# TestPoints.net
KiCad netlist of a schematic drawn in Altium Designer
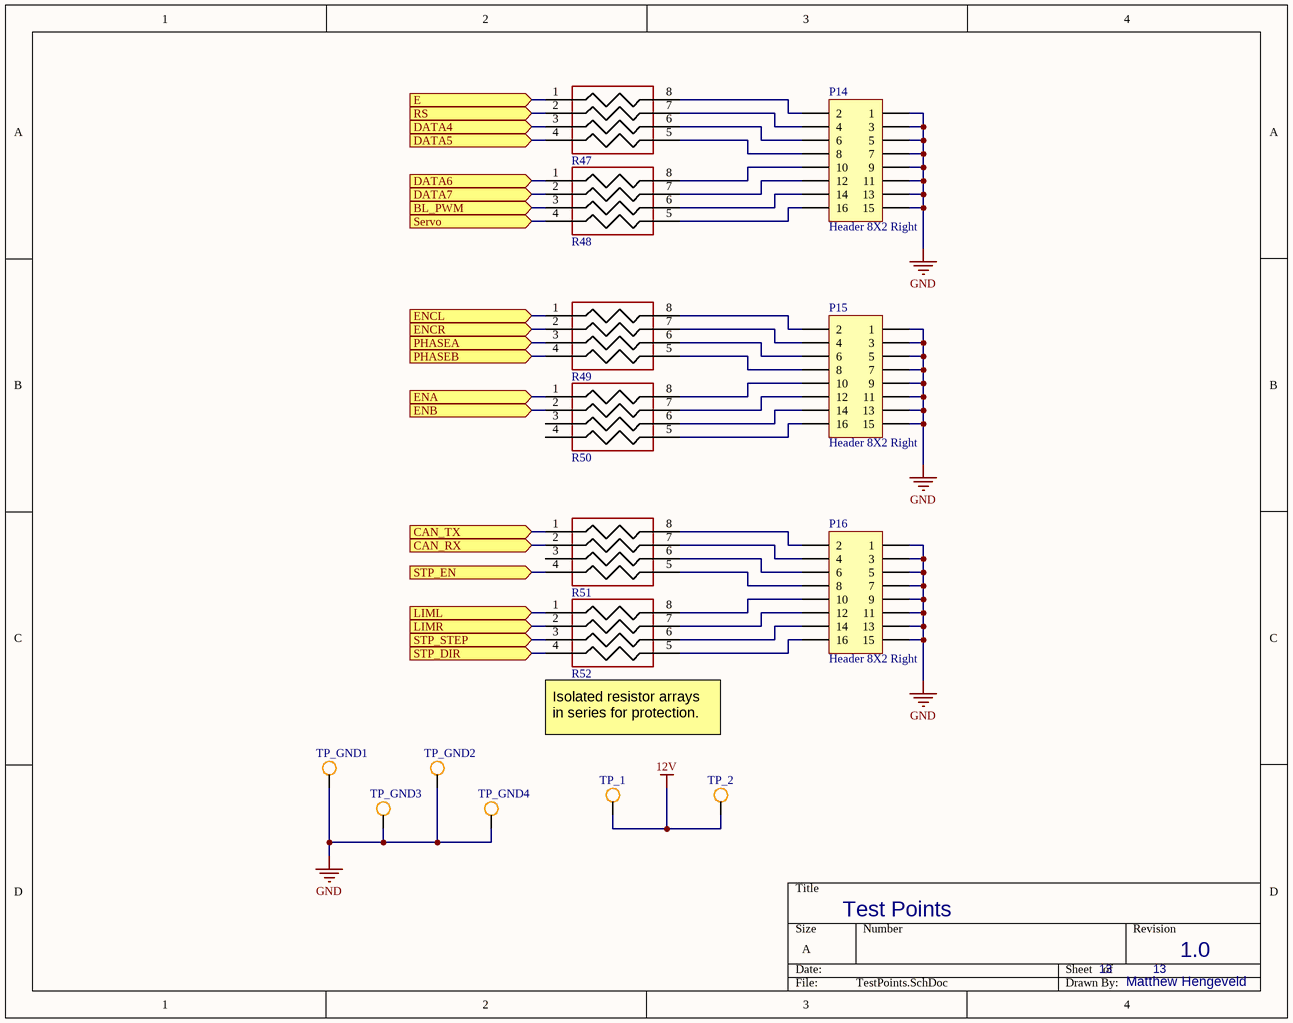
[diagram p0: TestPoints.SchDoc]

(export (version "E")
  (design (tool "Eeschema 10.0.6"))
  (components
    (comp (ref "P14")
      (value "Header 8X2 Right")
      (footprint "HDR2X8 RIGHT")
      (description "Header, 8-Pin, Dual row, Right Angle")
      (fields (field (name "PUBLISHER") "Altium Limited"))
      (libsource (lib "Hengeveld") (part "Header 8X2 Right"))
    )
    (comp (ref "P15")
      (value "Header 8X2 Right")
      (footprint "HDR2X8 RIGHT")
      (description "Header, 8-Pin, Dual row, Right Angle")
      (fields (field (name "PUBLISHER") "Altium Limited"))
      (libsource (lib "Hengeveld") (part "Header 8X2 Right"))
    )
    (comp (ref "P16")
      (value "Header 8X2 Right")
      (footprint "HDR2X8 RIGHT")
      (description "Header, 8-Pin, Dual row, Right Angle")
      (fields (field (name "PUBLISHER") "Altium Limited"))
      (libsource (lib "Hengeveld") (part "Header 8X2 Right"))
    )
    (comp (ref "R47")
      (value "8RES_ISO_ARRAY")
      (footprint "4RES_ARRAY_1206")
      (description "4 Resistor Array")
      (libsource (lib "Hengeveld") (part "8RES_ISO_ARRAY"))
    )
    (comp (ref "R48")
      (value "8RES_ISO_ARRAY")
      (footprint "4RES_ARRAY_1206")
      (description "4 Resistor Array")
      (libsource (lib "Hengeveld") (part "8RES_ISO_ARRAY"))
    )
    (comp (ref "R49")
      (value "8RES_ISO_ARRAY")
      (footprint "4RES_ARRAY_1206")
      (description "4 Resistor Array")
      (libsource (lib "Hengeveld") (part "8RES_ISO_ARRAY"))
    )
    (comp (ref "R50")
      (value "8RES_ISO_ARRAY")
      (footprint "4RES_ARRAY_1206")
      (description "4 Resistor Array")
      (libsource (lib "Hengeveld") (part "8RES_ISO_ARRAY"))
    )
    (comp (ref "R51")
      (value "8RES_ISO_ARRAY")
      (footprint "4RES_ARRAY_1206")
      (description "4 Resistor Array")
      (libsource (lib "Hengeveld") (part "8RES_ISO_ARRAY"))
    )
    (comp (ref "R52")
      (value "8RES_ISO_ARRAY")
      (footprint "4RES_ARRAY_1206")
      (description "4 Resistor Array")
      (libsource (lib "Hengeveld") (part "8RES_ISO_ARRAY"))
    )
    (comp (ref "TP_1")
      (value "Test point")
      (footprint "SMD Test Hook")
      (libsource (lib "Hengeveld") (part "Test Point"))
    )
    (comp (ref "TP_2")
      (value "Test point")
      (footprint "SMD Test Hook")
      (libsource (lib "Hengeveld") (part "Test Point"))
    )
    (comp (ref "TP_GND1")
      (value "Test point")
      (footprint "SMD Test Hook")
      (libsource (lib "Hengeveld") (part "Test Point"))
    )
    (comp (ref "TP_GND2")
      (value "Test point")
      (footprint "SMD Test Hook")
      (libsource (lib "Hengeveld") (part "Test Point"))
    )
    (comp (ref "TP_GND3")
      (value "Test point")
      (footprint "SMD Test Hook")
      (libsource (lib "Hengeveld") (part "Test Point"))
    )
    (comp (ref "TP_GND4")
      (value "Test point")
      (footprint "SMD Test Hook")
      (libsource (lib "Hengeveld") (part "Test Point"))
    )
  )
  (nets
    (net (code "1") (name "/BL_PWM") (class "Default")
      (node (ref "R48") (pin "3") (pinfunction "14_3") (pintype "passive"))
    )
    (net (code "2") (name "/CAN_RX") (class "Default")
      (node (ref "R51") (pin "2") (pinfunction "14_2") (pintype "passive"))
    )
    (net (code "3") (name "/CAN_TX") (class "Default")
      (node (ref "R51") (pin "1") (pinfunction "14_1") (pintype "passive"))
    )
    (net (code "4") (name "/DATA4") (class "Default")
      (node (ref "R47") (pin "3") (pinfunction "14_3") (pintype "passive"))
    )
    (net (code "5") (name "/DATA5") (class "Default")
      (node (ref "R47") (pin "4") (pinfunction "14_4") (pintype "passive"))
    )
    (net (code "6") (name "/DATA6") (class "Default")
      (node (ref "R48") (pin "1") (pinfunction "14_1") (pintype "passive"))
    )
    (net (code "7") (name "/DATA7") (class "Default")
      (node (ref "R48") (pin "2") (pinfunction "14_2") (pintype "passive"))
    )
    (net (code "8") (name "/E") (class "Default")
      (node (ref "R47") (pin "1") (pinfunction "14_1") (pintype "passive"))
    )
    (net (code "9") (name "/ENA") (class "Default")
      (node (ref "R50") (pin "1") (pinfunction "14_1") (pintype "passive"))
    )
    (net (code "10") (name "/ENB") (class "Default")
      (node (ref "R50") (pin "2") (pinfunction "14_2") (pintype "passive"))
    )
    (net (code "11") (name "/ENCL") (class "Default")
      (node (ref "R49") (pin "1") (pinfunction "14_1") (pintype "passive"))
    )
    (net (code "12") (name "/ENCR") (class "Default")
      (node (ref "R49") (pin "2") (pinfunction "14_2") (pintype "passive"))
    )
    (net (code "13") (name "/LIML") (class "Default")
      (node (ref "R52") (pin "1") (pinfunction "14_1") (pintype "passive"))
    )
    (net (code "14") (name "/LIMR") (class "Default")
      (node (ref "R52") (pin "2") (pinfunction "14_2") (pintype "passive"))
    )
    (net (code "15") (name "/PHASEA") (class "Default")
      (node (ref "R49") (pin "3") (pinfunction "14_3") (pintype "passive"))
    )
    (net (code "16") (name "/PHASEB") (class "Default")
      (node (ref "R49") (pin "4") (pinfunction "14_4") (pintype "passive"))
    )
    (net (code "17") (name "/RS") (class "Default")
      (node (ref "R47") (pin "2") (pinfunction "14_2") (pintype "passive"))
    )
    (net (code "18") (name "/STP_DIR") (class "Default")
      (node (ref "R52") (pin "4") (pinfunction "14_4") (pintype "passive"))
    )
    (net (code "19") (name "/STP_EN") (class "Default")
      (node (ref "R51") (pin "4") (pinfunction "14_4") (pintype "passive"))
    )
    (net (code "20") (name "/STP_STEP") (class "Default")
      (node (ref "R52") (pin "3") (pinfunction "14_3") (pintype "passive"))
    )
    (net (code "21") (name "/Servo") (class "Default")
      (node (ref "R48") (pin "4") (pinfunction "14_4") (pintype "passive"))
    )
    (net (code "22") (name "12V") (class "Default")
      (node (ref "TP_1") (pin "1") (pinfunction "point_1") (pintype "passive"))
      (node (ref "TP_2") (pin "1") (pinfunction "point_1") (pintype "passive"))
    )
    (net (code "23") (name "GND") (class "Default")
      (node (ref "P14") (pin "1") (pinfunction "1_1") (pintype "passive"))
      (node (ref "P14") (pin "11") (pinfunction "11_11") (pintype "passive"))
      (node (ref "P14") (pin "13") (pinfunction "13_13") (pintype "passive"))
      (node (ref "P14") (pin "15") (pinfunction "15_15") (pintype "passive"))
      (node (ref "P14") (pin "3") (pinfunction "3_3") (pintype "passive"))
      (node (ref "P14") (pin "5") (pinfunction "5_5") (pintype "passive"))
      (node (ref "P14") (pin "7") (pinfunction "7_7") (pintype "passive"))
      (node (ref "P14") (pin "9") (pinfunction "9_9") (pintype "passive"))
      (node (ref "P15") (pin "1") (pinfunction "1_1") (pintype "passive"))
      (node (ref "P15") (pin "11") (pinfunction "11_11") (pintype "passive"))
      (node (ref "P15") (pin "13") (pinfunction "13_13") (pintype "passive"))
      (node (ref "P15") (pin "15") (pinfunction "15_15") (pintype "passive"))
      (node (ref "P15") (pin "3") (pinfunction "3_3") (pintype "passive"))
      (node (ref "P15") (pin "5") (pinfunction "5_5") (pintype "passive"))
      (node (ref "P15") (pin "7") (pinfunction "7_7") (pintype "passive"))
      (node (ref "P15") (pin "9") (pinfunction "9_9") (pintype "passive"))
      (node (ref "P16") (pin "1") (pinfunction "1_1") (pintype "passive"))
      (node (ref "P16") (pin "11") (pinfunction "11_11") (pintype "passive"))
      (node (ref "P16") (pin "13") (pinfunction "13_13") (pintype "passive"))
      (node (ref "P16") (pin "15") (pinfunction "15_15") (pintype "passive"))
      (node (ref "P16") (pin "3") (pinfunction "3_3") (pintype "passive"))
      (node (ref "P16") (pin "5") (pinfunction "5_5") (pintype "passive"))
      (node (ref "P16") (pin "7") (pinfunction "7_7") (pintype "passive"))
      (node (ref "P16") (pin "9") (pinfunction "9_9") (pintype "passive"))
      (node (ref "TP_GND1") (pin "1") (pinfunction "point_1") (pintype "passive"))
      (node (ref "TP_GND2") (pin "1") (pinfunction "point_1") (pintype "passive"))
      (node (ref "TP_GND3") (pin "1") (pinfunction "point_1") (pintype "passive"))
      (node (ref "TP_GND4") (pin "1") (pinfunction "point_1") (pintype "passive"))
    )
    (net (code "24") (name "Net-(P14-Pad2)") (class "Default")
      (node (ref "P14") (pin "2") (pinfunction "2_2") (pintype "passive"))
      (node (ref "R47") (pin "8") (pinfunction "15_8") (pintype "passive"))
    )
    (net (code "25") (name "Net-(P14-Pad4)") (class "Default")
      (node (ref "P14") (pin "4") (pinfunction "4_4") (pintype "passive"))
      (node (ref "R47") (pin "7") (pinfunction "15_7") (pintype "passive"))
    )
    (net (code "26") (name "Net-(P14-Pad6)") (class "Default")
      (node (ref "P14") (pin "6") (pinfunction "6_6") (pintype "passive"))
      (node (ref "R47") (pin "6") (pinfunction "15_6") (pintype "passive"))
    )
    (net (code "27") (name "Net-(P14-Pad8)") (class "Default")
      (node (ref "P14") (pin "8") (pinfunction "8_8") (pintype "passive"))
      (node (ref "R47") (pin "5") (pinfunction "15_5") (pintype "passive"))
    )
    (net (code "28") (name "Net-(P14-Pad10)") (class "Default")
      (node (ref "P14") (pin "10") (pinfunction "10_10") (pintype "passive"))
      (node (ref "R48") (pin "8") (pinfunction "15_8") (pintype "passive"))
    )
    (net (code "29") (name "Net-(P14-Pad12)") (class "Default")
      (node (ref "P14") (pin "12") (pinfunction "12_12") (pintype "passive"))
      (node (ref "R48") (pin "7") (pinfunction "15_7") (pintype "passive"))
    )
    (net (code "30") (name "Net-(P14-Pad14)") (class "Default")
      (node (ref "P14") (pin "14") (pinfunction "14_14") (pintype "passive"))
      (node (ref "R48") (pin "6") (pinfunction "15_6") (pintype "passive"))
    )
    (net (code "31") (name "Net-(P14-Pad16)") (class "Default")
      (node (ref "P14") (pin "16") (pinfunction "16_16") (pintype "passive"))
      (node (ref "R48") (pin "5") (pinfunction "15_5") (pintype "passive"))
    )
    (net (code "32") (name "Net-(P15-Pad2)") (class "Default")
      (node (ref "P15") (pin "2") (pinfunction "2_2") (pintype "passive"))
      (node (ref "R49") (pin "8") (pinfunction "15_8") (pintype "passive"))
    )
    (net (code "33") (name "Net-(P15-Pad4)") (class "Default")
      (node (ref "P15") (pin "4") (pinfunction "4_4") (pintype "passive"))
      (node (ref "R49") (pin "7") (pinfunction "15_7") (pintype "passive"))
    )
    (net (code "34") (name "Net-(P15-Pad6)") (class "Default")
      (node (ref "P15") (pin "6") (pinfunction "6_6") (pintype "passive"))
      (node (ref "R49") (pin "6") (pinfunction "15_6") (pintype "passive"))
    )
    (net (code "35") (name "Net-(P15-Pad8)") (class "Default")
      (node (ref "P15") (pin "8") (pinfunction "8_8") (pintype "passive"))
      (node (ref "R49") (pin "5") (pinfunction "15_5") (pintype "passive"))
    )
    (net (code "36") (name "Net-(P15-Pad10)") (class "Default")
      (node (ref "P15") (pin "10") (pinfunction "10_10") (pintype "passive"))
      (node (ref "R50") (pin "8") (pinfunction "15_8") (pintype "passive"))
    )
    (net (code "37") (name "Net-(P15-Pad12)") (class "Default")
      (node (ref "P15") (pin "12") (pinfunction "12_12") (pintype "passive"))
      (node (ref "R50") (pin "7") (pinfunction "15_7") (pintype "passive"))
    )
    (net (code "38") (name "Net-(P15-Pad14)") (class "Default")
      (node (ref "P15") (pin "14") (pinfunction "14_14") (pintype "passive"))
      (node (ref "R50") (pin "6") (pinfunction "15_6") (pintype "passive"))
    )
    (net (code "39") (name "Net-(P15-Pad16)") (class "Default")
      (node (ref "P15") (pin "16") (pinfunction "16_16") (pintype "passive"))
      (node (ref "R50") (pin "5") (pinfunction "15_5") (pintype "passive"))
    )
    (net (code "40") (name "Net-(P16-Pad2)") (class "Default")
      (node (ref "P16") (pin "2") (pinfunction "2_2") (pintype "passive"))
      (node (ref "R51") (pin "8") (pinfunction "15_8") (pintype "passive"))
    )
    (net (code "41") (name "Net-(P16-Pad4)") (class "Default")
      (node (ref "P16") (pin "4") (pinfunction "4_4") (pintype "passive"))
      (node (ref "R51") (pin "7") (pinfunction "15_7") (pintype "passive"))
    )
    (net (code "42") (name "Net-(P16-Pad6)") (class "Default")
      (node (ref "P16") (pin "6") (pinfunction "6_6") (pintype "passive"))
      (node (ref "R51") (pin "6") (pinfunction "15_6") (pintype "passive"))
    )
    (net (code "43") (name "Net-(P16-Pad8)") (class "Default")
      (node (ref "P16") (pin "8") (pinfunction "8_8") (pintype "passive"))
      (node (ref "R51") (pin "5") (pinfunction "15_5") (pintype "passive"))
    )
    (net (code "44") (name "Net-(P16-Pad10)") (class "Default")
      (node (ref "P16") (pin "10") (pinfunction "10_10") (pintype "passive"))
      (node (ref "R52") (pin "8") (pinfunction "15_8") (pintype "passive"))
    )
    (net (code "45") (name "Net-(P16-Pad12)") (class "Default")
      (node (ref "P16") (pin "12") (pinfunction "12_12") (pintype "passive"))
      (node (ref "R52") (pin "7") (pinfunction "15_7") (pintype "passive"))
    )
    (net (code "46") (name "Net-(P16-Pad14)") (class "Default")
      (node (ref "P16") (pin "14") (pinfunction "14_14") (pintype "passive"))
      (node (ref "R52") (pin "6") (pinfunction "15_6") (pintype "passive"))
    )
    (net (code "47") (name "Net-(P16-Pad16)") (class "Default")
      (node (ref "P16") (pin "16") (pinfunction "16_16") (pintype "passive"))
      (node (ref "R52") (pin "5") (pinfunction "15_5") (pintype "passive"))
    )
    (net (code "48") (name "unconnected-(R50-14-Pad3)") (class "Default")
      (node (ref "R50") (pin "3") (pinfunction "14_3") (pintype "passive"))
    )
    (net (code "49") (name "unconnected-(R50-14-Pad4)") (class "Default")
      (node (ref "R50") (pin "4") (pinfunction "14_4") (pintype "passive"))
    )
    (net (code "50") (name "unconnected-(R51-14-Pad3)") (class "Default")
      (node (ref "R51") (pin "3") (pinfunction "14_3") (pintype "passive"))
    )
  )
)
